# 13-Experimental.net
KiCad netlist of a schematic drawn in Altium Designer
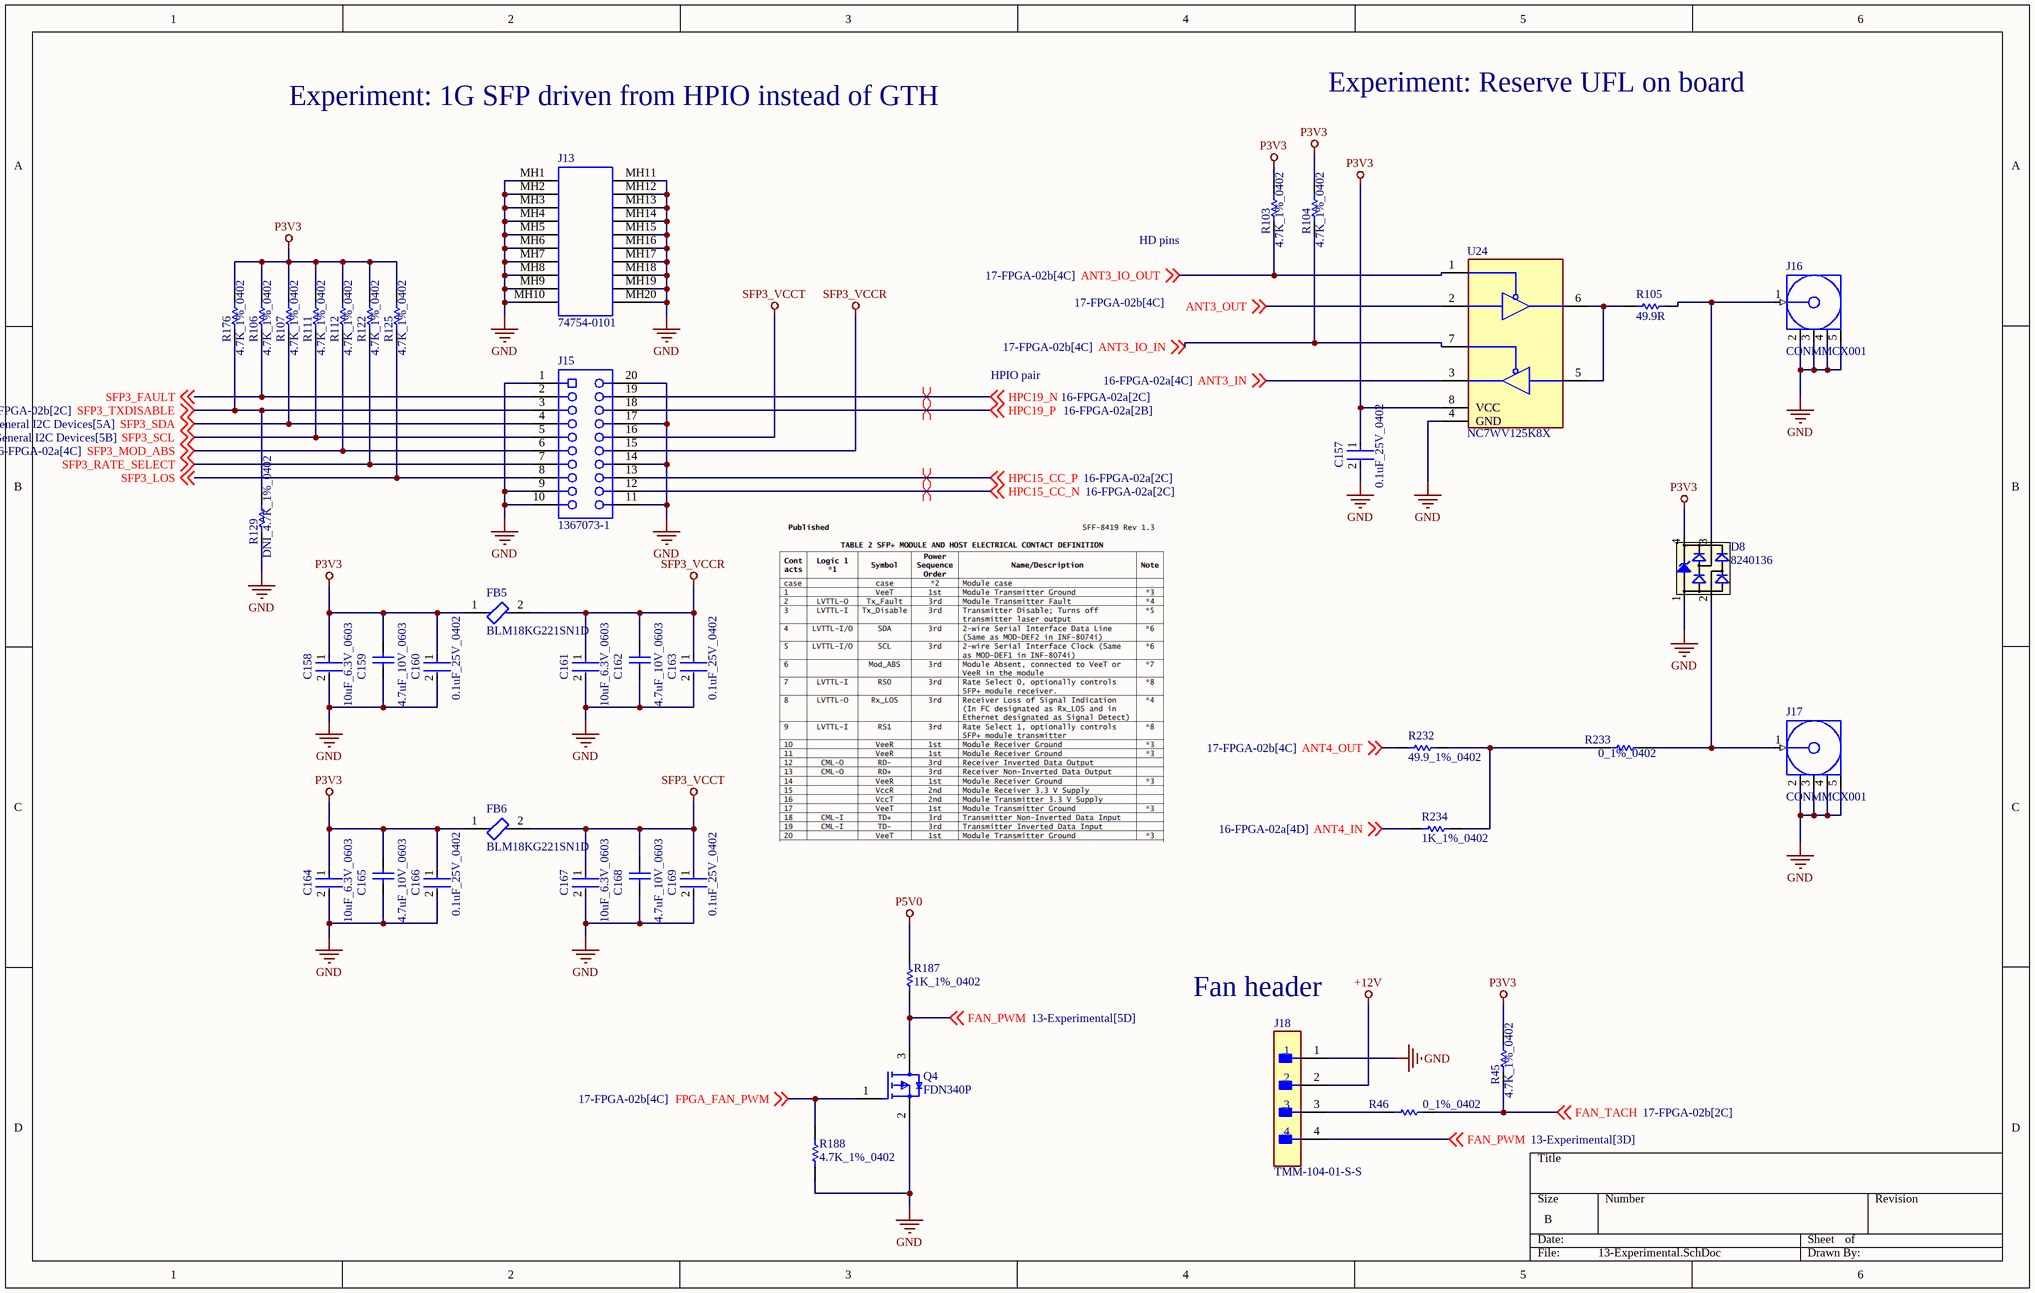
[diagram p0: 13-Experimental.SchDoc]

(export (version "E")
  (design (tool "Eeschema 10.0.6"))
  (components
    (comp (ref "C157")
      (value "0.1uF_25V_0402")
      (footprint "FP-0402-L_1_0_1-W_0_5_0_1-IPC_C")
      (description "General Purpose Ceramic Capacitor, 0402, 100nF, 10%, X7R, 15%, 25V")
      (fields (field (name "VOLTAGE") "25V") (field (name "TOLERANCE") "10%"))
      (libsource (lib "Altium Content Vault") (part "b4654b650e69147ec39a6b967a45e02"))
    )
    (comp (ref "C158")
      (value "10uF_6.3V_0603")
      (footprint "FP-C0603C106M9PACTU-MFG")
      (description "CAP CER 10UF 6.3V X5R 0603")
      (fields
        (field (name "MANUFACTURER PART NUMBER") "C0603C106M9PACTU")
        (field (name "MANUFACTURER") "Kemet")
      )
      (libsource (lib "Altium Content Vault") (part "b4654b650e69147ec39a6b967a45e02"))
    )
    (comp (ref "C159")
      (value "4.7uF_10V_0603")
      (footprint "CAPC1608X87X35NL15T15")
      (fields (field (name "PART NUMBER") "C0603C475K8PACTU") (field (name "MANUFACTURER") "Kemet"))
      (libsource (lib "Altium Content Vault") (part "CAP"))
    )
    (comp (ref "C160")
      (value "0.1uF_25V_0402")
      (footprint "FP-0402-L_1_0_1-W_0_5_0_1-IPC_C")
      (description "General Purpose Ceramic Capacitor, 0402, 100nF, 10%, X7R, 15%, 25V")
      (fields (field (name "VOLTAGE") "25V") (field (name "TOLERANCE") "10%"))
      (libsource (lib "Altium Content Vault") (part "b4654b650e69147ec39a6b967a45e02"))
    )
    (comp (ref "C161")
      (value "10uF_6.3V_0603")
      (footprint "FP-C0603C106M9PACTU-MFG")
      (description "CAP CER 10UF 6.3V X5R 0603")
      (fields
        (field (name "MANUFACTURER PART NUMBER") "C0603C106M9PACTU")
        (field (name "MANUFACTURER") "Kemet")
      )
      (libsource (lib "Altium Content Vault") (part "b4654b650e69147ec39a6b967a45e02"))
    )
    (comp (ref "C162")
      (value "4.7uF_10V_0603")
      (footprint "CAPC1608X87X35NL15T15")
      (fields (field (name "PART NUMBER") "C0603C475K8PACTU") (field (name "MANUFACTURER") "Kemet"))
      (libsource (lib "Altium Content Vault") (part "CAP"))
    )
    (comp (ref "C163")
      (value "0.1uF_25V_0402")
      (footprint "FP-0402-L_1_0_1-W_0_5_0_1-IPC_C")
      (description "General Purpose Ceramic Capacitor, 0402, 100nF, 10%, X7R, 15%, 25V")
      (fields (field (name "VOLTAGE") "25V") (field (name "TOLERANCE") "10%"))
      (libsource (lib "Altium Content Vault") (part "b4654b650e69147ec39a6b967a45e02"))
    )
    (comp (ref "C164")
      (value "10uF_6.3V_0603")
      (footprint "FP-C0603C106M9PACTU-MFG")
      (description "CAP CER 10UF 6.3V X5R 0603")
      (fields
        (field (name "MANUFACTURER PART NUMBER") "C0603C106M9PACTU")
        (field (name "MANUFACTURER") "Kemet")
      )
      (libsource (lib "Altium Content Vault") (part "b4654b650e69147ec39a6b967a45e02"))
    )
    (comp (ref "C165")
      (value "4.7uF_10V_0603")
      (footprint "CAPC1608X87X35NL15T15")
      (fields (field (name "PART NUMBER") "C0603C475K8PACTU") (field (name "MANUFACTURER") "Kemet"))
      (libsource (lib "Altium Content Vault") (part "CAP"))
    )
    (comp (ref "C166")
      (value "0.1uF_25V_0402")
      (footprint "FP-0402-L_1_0_1-W_0_5_0_1-IPC_C")
      (description "General Purpose Ceramic Capacitor, 0402, 100nF, 10%, X7R, 15%, 25V")
      (fields (field (name "VOLTAGE") "25V") (field (name "TOLERANCE") "10%"))
      (libsource (lib "Altium Content Vault") (part "b4654b650e69147ec39a6b967a45e02"))
    )
    (comp (ref "C167")
      (value "10uF_6.3V_0603")
      (footprint "FP-C0603C106M9PACTU-MFG")
      (description "CAP CER 10UF 6.3V X5R 0603")
      (fields
        (field (name "MANUFACTURER PART NUMBER") "C0603C106M9PACTU")
        (field (name "MANUFACTURER") "Kemet")
      )
      (libsource (lib "Altium Content Vault") (part "b4654b650e69147ec39a6b967a45e02"))
    )
    (comp (ref "C168")
      (value "4.7uF_10V_0603")
      (footprint "CAPC1608X87X35NL15T15")
      (fields (field (name "PART NUMBER") "C0603C475K8PACTU") (field (name "MANUFACTURER") "Kemet"))
      (libsource (lib "Altium Content Vault") (part "CAP"))
    )
    (comp (ref "C169")
      (value "0.1uF_25V_0402")
      (footprint "FP-0402-L_1_0_1-W_0_5_0_1-IPC_C")
      (description "General Purpose Ceramic Capacitor, 0402, 100nF, 10%, X7R, 15%, 25V")
      (fields (field (name "VOLTAGE") "25V") (field (name "TOLERANCE") "10%"))
      (libsource (lib "Altium Content Vault") (part "b4654b650e69147ec39a6b967a45e02"))
    )
    (comp (ref "D8")
      (value "8240136")
      (footprint "SOT143-4L")
      (description "TVS Diode WE-TVS-HS, VRWM=3.3V")
      (fields (field (name "MANUFACTURER") "Wuerth Elektronik"))
      (libsource (lib "Altium Content Vault") (part "WE-TVS-HS-4"))
    )
    (comp (ref "FB5")
      (value "BLM18KG221SN1D")
      (footprint "FP-BLM18-0_15-t0_8-IPC_B")
      (description "Chip Ferrite Bead, 0603, 220Ω @ 100MHz, 0.05Ω, 25%, 2.2A")
      (fields (field (name "TOLERANCE") "25%"))
      (libsource (lib "Altium Content Vault") (part "5f30dd21d616792df468990f7003faa"))
    )
    (comp (ref "FB6")
      (value "BLM18KG221SN1D")
      (footprint "FP-BLM18-0_15-t0_8-IPC_B")
      (description "Chip Ferrite Bead, 0603, 220Ω @ 100MHz, 0.05Ω, 25%, 2.2A")
      (fields (field (name "TOLERANCE") "25%"))
      (libsource (lib "Altium Content Vault") (part "5f30dd21d616792df468990f7003faa"))
    )
    (comp (ref "J13")
      (value "74754-0101")
      (footprint "MOLX-74754-0101_V")
      (description "SFP+ Cage, Single Port, Height 10.85 mm, Tail Height 3.05 mm, -40 to 85 degC, RoHS, Tray")
      (libsource (lib "Altium Content Vault") (part "MOLX-74754-0101"))
    )
    (comp (ref "J15")
      (value "1367073-1")
      (footprint "TECO-1367073-1_V")
      (fields (field (name "MANUFACTURER") "TE Connectivity"))
      (libsource (lib "Altium Content Vault") (part "CN-2P-F-R20_B"))
    )
    (comp (ref "J16")
      (value "CONMMCX001")
      (footprint "CON-MMCX")
      (description "MMCX Female PCB Mount Connector, Thru-Hole")
      (libsource (lib "Altium Content Vault") (part "CN-1P-F-RF5"))
    )
    (comp (ref "J17")
      (value "CONMMCX001")
      (footprint "CON-MMCX")
      (description "MMCX Female PCB Mount Connector, Thru-Hole")
      (libsource (lib "Altium Content Vault") (part "CN-1P-F-RF5"))
    )
    (comp (ref "J18")
      (value "TMM-104-01-S-S")
      (footprint "FP-TMM-104-01-S-S-MFG")
      (description "CONN HEADER VERT 4POS 2MM")
      (libsource (lib "Altium Content Vault") (part "299a8cea1bdcbc3624fe62c390fa72c"))
    )
    (comp (ref "Q4")
      (value "FDN340P")
      (footprint "FP-527AG-MFG")
      (description "MOSFET P-CH 20V 2A SSOT3")
      (libsource (lib "Altium Content Vault") (part "d23f43cc42f60b967b7caccf14518fd"))
    )
    (comp (ref "R45")
      (value "4.7K_1%_0402")
      (footprint "RESC1005X40X25NL10T10")
      (fields (field (name "MANUFACTURER") "Bourns") (field (name "PART NUMBER") "CR0402-FX-4701GLF"))
      (libsource (lib "Altium Content Vault") (part "RES"))
    )
    (comp (ref "R46")
      (value "0_1%_0402")
      (footprint "RESC1005X40X25LL05T05")
      (description "Chip Resistor, 0 Ohm, 0.1 W, -55 to 155 degC, 0402 (1005 Metric), RoHS, Tape and Reel")
      (fields (field (name "MANUFACTURER") "Panasonic") (field (name "TOLERANCE") "5%"))
      (libsource (lib "Altium Content Vault") (part "RES-2"))
    )
    (comp (ref "R103")
      (value "4.7K_1%_0402")
      (footprint "RESC1005X40X25NL10T10")
      (fields (field (name "MANUFACTURER") "Bourns") (field (name "PART NUMBER") "CR0402-FX-4701GLF"))
      (libsource (lib "Altium Content Vault") (part "RES"))
    )
    (comp (ref "R104")
      (value "4.7K_1%_0402")
      (footprint "RESC1005X40X25NL10T10")
      (fields (field (name "MANUFACTURER") "Bourns") (field (name "PART NUMBER") "CR0402-FX-4701GLF"))
      (libsource (lib "Altium Content Vault") (part "RES"))
    )
    (comp (ref "R105")
      (value "49.9R")
      (footprint "RESC1608X55X25NL10T15")
      (libsource (lib "Altium Content Vault") (part "RES-2"))
    )
    (comp (ref "R106")
      (value "4.7K_1%_0402")
      (footprint "RESC1005X40X25NL10T10")
      (fields (field (name "MANUFACTURER") "Bourns") (field (name "PART NUMBER") "CR0402-FX-4701GLF"))
      (libsource (lib "Altium Content Vault") (part "RES"))
    )
    (comp (ref "R107")
      (value "4.7K_1%_0402")
      (footprint "RESC1005X40X25NL10T10")
      (fields (field (name "MANUFACTURER") "Bourns") (field (name "PART NUMBER") "CR0402-FX-4701GLF"))
      (libsource (lib "Altium Content Vault") (part "RES"))
    )
    (comp (ref "R111")
      (value "4.7K_1%_0402")
      (footprint "RESC1005X40X25NL10T10")
      (fields (field (name "MANUFACTURER") "Bourns") (field (name "PART NUMBER") "CR0402-FX-4701GLF"))
      (libsource (lib "Altium Content Vault") (part "RES"))
    )
    (comp (ref "R112")
      (value "4.7K_1%_0402")
      (footprint "RESC1005X40X25NL10T10")
      (fields (field (name "MANUFACTURER") "Bourns") (field (name "PART NUMBER") "CR0402-FX-4701GLF"))
      (libsource (lib "Altium Content Vault") (part "RES"))
    )
    (comp (ref "R122")
      (value "4.7K_1%_0402")
      (footprint "RESC1005X40X25NL10T10")
      (fields (field (name "MANUFACTURER") "Bourns") (field (name "PART NUMBER") "CR0402-FX-4701GLF"))
      (libsource (lib "Altium Content Vault") (part "RES"))
    )
    (comp (ref "R125")
      (value "4.7K_1%_0402")
      (footprint "RESC1005X40X25NL10T10")
      (fields (field (name "MANUFACTURER") "Bourns") (field (name "PART NUMBER") "CR0402-FX-4701GLF"))
      (libsource (lib "Altium Content Vault") (part "RES"))
    )
    (comp (ref "R129")
      (value "DNI_4.7K_1%_0402")
      (footprint "RESC1005X40X25NL10T10")
      (fields (field (name "MANUFACTURER") "Bourns") (field (name "PART NUMBER") "CR0402-FX-4701GLF"))
      (libsource (lib "Altium Content Vault") (part "RES"))
    )
    (comp (ref "R176")
      (value "4.7K_1%_0402")
      (footprint "RESC1005X40X25NL10T10")
      (fields (field (name "MANUFACTURER") "Bourns") (field (name "PART NUMBER") "CR0402-FX-4701GLF"))
      (libsource (lib "Altium Content Vault") (part "RES"))
    )
    (comp (ref "R187")
      (value "1K_1%_0402")
      (footprint "RESC1005X40X25NL05T05")
      (fields (field (name "MANUFACTURER") "Vishay Dale") (field (name "PART NUMBER") "CRCW04021K00FKTD"))
      (libsource (lib "Altium Content Vault") (part "RES"))
    )
    (comp (ref "R188")
      (value "4.7K_1%_0402")
      (footprint "RESC1005X40X25NL10T10")
      (fields (field (name "MANUFACTURER") "Bourns") (field (name "PART NUMBER") "CR0402-FX-4701GLF"))
      (libsource (lib "Altium Content Vault") (part "RES"))
    )
    (comp (ref "R232")
      (value "49.9_1%_0402")
      (footprint "RESC1005X40X25NL10T10")
      (fields (field (name "PART NUMBER") "RK73H1ETTP49R9F") (field (name "MANUFACTURER") "KOA Speer"))
      (libsource (lib "Altium Content Vault") (part "RES"))
    )
    (comp (ref "R233")
      (value "0_1%_0402")
      (footprint "RESC1005X40X25LL05T05")
      (description "Chip Resistor, 0 Ohm, 0.1 W, -55 to 155 degC, 0402 (1005 Metric), RoHS, Tape and Reel")
      (fields (field (name "MANUFACTURER") "Panasonic") (field (name "TOLERANCE") "5%"))
      (libsource (lib "Altium Content Vault") (part "RES-2"))
    )
    (comp (ref "R234")
      (value "1K_1%_0402")
      (footprint "RESC1005X40X25NL05T05")
      (fields (field (name "MANUFACTURER") "Vishay Dale") (field (name "PART NUMBER") "CRCW04021K00FKTD"))
      (libsource (lib "Altium Content Vault") (part "RES"))
    )
    (comp (ref "U24")
      (value "NC7WV125K8X")
      (footprint "SOP50P310X90-8N")
      (description "Integrated Circuit")
      (fields (field (name "MOUSER PART NUMBER") "512-NC7WV125K8X"))
      (libsource (lib "SamacSys") (part "NC7WV125K8X"))
    )
  )
  (nets
    (net (code "1") (name "+12V") (class "Default")
      (node (ref "J18") (pin "2") (pinfunction "2_2") (pintype "passive"))
    )
    (net (code "2") (name "ANT3_IN") (class "Default") (node (ref "U24") (pin "3") (pintype "passive")))
    (net (code "3") (name "ANT3_IO_IN") (class "Default")
      (node (ref "R104") (pin "2") (pinfunction "2_2") (pintype "passive"))
      (node (ref "U24") (pin "7") (pintype "passive"))
    )
    (net (code "4") (name "ANT3_IO_OUT") (class "Default")
      (node (ref "R103") (pin "2") (pinfunction "2_2") (pintype "passive"))
      (node (ref "U24") (pin "1") (pintype "passive"))
    )
    (net (code "5") (name "ANT3_OUT") (class "Default") (node (ref "U24") (pin "2") (pintype "passive")))
    (net (code "6") (name "ANT4_IN") (class "Default")
      (node (ref "R234") (pin "1") (pinfunction "1_1") (pintype "passive"))
    )
    (net (code "7") (name "ANT4_OUT") (class "Default")
      (node (ref "R232") (pin "1") (pinfunction "1_1") (pintype "passive"))
    )
    (net (code "8") (name "FAN_PWM") (class "Default")
      (node (ref "J18") (pin "4") (pinfunction "4_4") (pintype "passive"))
      (node (ref "Q4") (pin "3") (pinfunction "D_3") (pintype "passive"))
      (node (ref "R187") (pin "1") (pinfunction "1_1") (pintype "passive"))
    )
    (net (code "9") (name "FAN_TACH") (class "Default")
      (node (ref "R45") (pin "2") (pinfunction "2_2") (pintype "passive"))
      (node (ref "R46") (pin "2") (pinfunction "2_2") (pintype "passive"))
    )
    (net (code "10") (name "FPGA_FAN_PWM") (class "Default")
      (node (ref "Q4") (pin "1") (pinfunction "G_1") (pintype "passive"))
      (node (ref "R188") (pin "2") (pinfunction "2_2") (pintype "passive"))
    )
    (net (code "11") (name "GND") (class "Default")
      (node (ref "C157") (pin "2") (pinfunction "2_2") (pintype "passive"))
      (node (ref "C158") (pin "2") (pinfunction "2_2") (pintype "passive"))
      (node (ref "C159") (pin "1") (pinfunction "1_1") (pintype "passive"))
      (node (ref "C160") (pin "2") (pinfunction "2_2") (pintype "passive"))
      (node (ref "C161") (pin "2") (pinfunction "2_2") (pintype "passive"))
      (node (ref "C162") (pin "1") (pinfunction "1_1") (pintype "passive"))
      (node (ref "C163") (pin "2") (pinfunction "2_2") (pintype "passive"))
      (node (ref "C164") (pin "2") (pinfunction "2_2") (pintype "passive"))
      (node (ref "C165") (pin "1") (pinfunction "1_1") (pintype "passive"))
      (node (ref "C166") (pin "2") (pinfunction "2_2") (pintype "passive"))
      (node (ref "C167") (pin "2") (pinfunction "2_2") (pintype "passive"))
      (node (ref "C168") (pin "1") (pinfunction "1_1") (pintype "passive"))
      (node (ref "C169") (pin "2") (pinfunction "2_2") (pintype "passive"))
      (node (ref "D8") (pin "1") (pinfunction "GND_1") (pintype "passive"))
      (node (ref "J13") (pin "MH1") (pinfunction "MH1_MH1") (pintype "passive"))
      (node (ref "J13") (pin "MH10") (pinfunction "MH10_MH10") (pintype "passive"))
      (node (ref "J13") (pin "MH11") (pinfunction "MH11_MH11") (pintype "passive"))
      (node (ref "J13") (pin "MH12") (pinfunction "MH12_MH12") (pintype "passive"))
      (node (ref "J13") (pin "MH13") (pinfunction "MH13_MH13") (pintype "passive"))
      (node (ref "J13") (pin "MH14") (pinfunction "MH14_MH14") (pintype "passive"))
      (node (ref "J13") (pin "MH15") (pinfunction "MH15_MH15") (pintype "passive"))
      (node (ref "J13") (pin "MH16") (pinfunction "MH16_MH16") (pintype "passive"))
      (node (ref "J13") (pin "MH17") (pinfunction "MH17_MH17") (pintype "passive"))
      (node (ref "J13") (pin "MH18") (pinfunction "MH18_MH18") (pintype "passive"))
      (node (ref "J13") (pin "MH19") (pinfunction "MH19_MH19") (pintype "passive"))
      (node (ref "J13") (pin "MH2") (pinfunction "MH2_MH2") (pintype "passive"))
      (node (ref "J13") (pin "MH20") (pinfunction "MH20_MH20") (pintype "passive"))
      (node (ref "J13") (pin "MH3") (pinfunction "MH3_MH3") (pintype "passive"))
      (node (ref "J13") (pin "MH4") (pinfunction "MH4_MH4") (pintype "passive"))
      (node (ref "J13") (pin "MH5") (pinfunction "MH5_MH5") (pintype "passive"))
      (node (ref "J13") (pin "MH6") (pinfunction "MH6_MH6") (pintype "passive"))
      (node (ref "J13") (pin "MH7") (pinfunction "MH7_MH7") (pintype "passive"))
      (node (ref "J13") (pin "MH8") (pinfunction "MH8_MH8") (pintype "passive"))
      (node (ref "J13") (pin "MH9") (pinfunction "MH9_MH9") (pintype "passive"))
      (node (ref "J15") (pin "1") (pinfunction "1_1") (pintype "passive"))
      (node (ref "J15") (pin "10") (pinfunction "10_10") (pintype "passive"))
      (node (ref "J15") (pin "11") (pinfunction "11_11") (pintype "passive"))
      (node (ref "J15") (pin "14") (pinfunction "14_14") (pintype "passive"))
      (node (ref "J15") (pin "17") (pinfunction "17_17") (pintype "passive"))
      (node (ref "J15") (pin "20") (pinfunction "20_20") (pintype "passive"))
      (node (ref "J15") (pin "9") (pinfunction "9_9") (pintype "passive"))
      (node (ref "J16") (pin "2") (pinfunction "GND_2") (pintype "power_in"))
      (node (ref "J16") (pin "3") (pinfunction "GND_3") (pintype "power_in"))
      (node (ref "J16") (pin "4") (pinfunction "GND_4") (pintype "power_in"))
      (node (ref "J16") (pin "5") (pinfunction "GND_5") (pintype "power_in"))
      (node (ref "J17") (pin "2") (pinfunction "GND_2") (pintype "power_in"))
      (node (ref "J17") (pin "3") (pinfunction "GND_3") (pintype "power_in"))
      (node (ref "J17") (pin "4") (pinfunction "GND_4") (pintype "power_in"))
      (node (ref "J17") (pin "5") (pinfunction "GND_5") (pintype "power_in"))
      (node (ref "J18") (pin "1") (pinfunction "1_1") (pintype "passive"))
      (node (ref "Q4") (pin "2") (pinfunction "S_2") (pintype "passive"))
      (node (ref "R129") (pin "2") (pinfunction "2_2") (pintype "passive"))
      (node (ref "R188") (pin "1") (pinfunction "1_1") (pintype "passive"))
      (node (ref "U24") (pin "4") (pinfunction "GND_4") (pintype "passive"))
    )
    (net (code "12") (name "HPC15_CC_N") (class "Default")
      (node (ref "J15") (pin "12") (pinfunction "12_12") (pintype "passive"))
    )
    (net (code "13") (name "HPC15_CC_P") (class "Default")
      (node (ref "J15") (pin "13") (pinfunction "13_13") (pintype "passive"))
    )
    (net (code "14") (name "HPC19_N") (class "Default")
      (node (ref "J15") (pin "19") (pinfunction "19_19") (pintype "passive"))
    )
    (net (code "15") (name "HPC19_P") (class "Default")
      (node (ref "J15") (pin "18") (pinfunction "18_18") (pintype "passive"))
    )
    (net (code "16") (name "Net-(D8-I{slash}O1)") (class "Default")
      (node (ref "D8") (pin "2") (pinfunction "I/O1_2") (pintype "passive"))
      (node (ref "J17") (pin "1") (pinfunction "Signal_1") (pintype "input"))
      (node (ref "R233") (pin "2") (pinfunction "2_2") (pintype "passive"))
    )
    (net (code "17") (name "Net-(D8-I{slash}O2)") (class "Default")
      (node (ref "D8") (pin "3") (pinfunction "I/O2_3") (pintype "passive"))
      (node (ref "J16") (pin "1") (pinfunction "Signal_1") (pintype "input"))
      (node (ref "R105") (pin "2") (pinfunction "2_2") (pintype "passive"))
    )
    (net (code "18") (name "Net-(J18-Pad3)") (class "Default")
      (node (ref "J18") (pin "3") (pinfunction "3_3") (pintype "passive"))
      (node (ref "R46") (pin "1") (pinfunction "1_1") (pintype "passive"))
    )
    (net (code "19") (name "Net-(R105-Pad1)") (class "Default")
      (node (ref "R105") (pin "1") (pinfunction "1_1") (pintype "passive"))
      (node (ref "U24") (pin "5") (pintype "passive"))
      (node (ref "U24") (pin "6") (pintype "passive"))
    )
    (net (code "20") (name "Net-(R232-Pad2)") (class "Default")
      (node (ref "R232") (pin "2") (pinfunction "2_2") (pintype "passive"))
      (node (ref "R233") (pin "1") (pinfunction "1_1") (pintype "passive"))
      (node (ref "R234") (pin "2") (pinfunction "2_2") (pintype "passive"))
    )
    (net (code "21") (name "P3V3") (class "Default")
      (node (ref "C157") (pin "1") (pinfunction "1_1") (pintype "passive"))
      (node (ref "C158") (pin "1") (pinfunction "1_1") (pintype "passive"))
      (node (ref "C159") (pin "2") (pinfunction "2_2") (pintype "passive"))
      (node (ref "C160") (pin "1") (pinfunction "1_1") (pintype "passive"))
      (node (ref "C164") (pin "1") (pinfunction "1_1") (pintype "passive"))
      (node (ref "C165") (pin "2") (pinfunction "2_2") (pintype "passive"))
      (node (ref "C166") (pin "1") (pinfunction "1_1") (pintype "passive"))
      (node (ref "D8") (pin "4") (pinfunction "VDD_4") (pintype "passive"))
      (node (ref "FB5") (pin "1") (pinfunction "1_1") (pintype "passive"))
      (node (ref "FB6") (pin "1") (pinfunction "1_1") (pintype "passive"))
      (node (ref "R103") (pin "1") (pinfunction "1_1") (pintype "passive"))
      (node (ref "R104") (pin "1") (pinfunction "1_1") (pintype "passive"))
      (node (ref "R106") (pin "1") (pinfunction "1_1") (pintype "passive"))
      (node (ref "R107") (pin "1") (pinfunction "1_1") (pintype "passive"))
      (node (ref "R111") (pin "1") (pinfunction "1_1") (pintype "passive"))
      (node (ref "R112") (pin "1") (pinfunction "1_1") (pintype "passive"))
      (node (ref "R122") (pin "1") (pinfunction "1_1") (pintype "passive"))
      (node (ref "R125") (pin "1") (pinfunction "1_1") (pintype "passive"))
      (node (ref "R176") (pin "1") (pinfunction "1_1") (pintype "passive"))
      (node (ref "R45") (pin "1") (pinfunction "1_1") (pintype "passive"))
      (node (ref "U24") (pin "8") (pinfunction "VCC_8") (pintype "passive"))
    )
    (net (code "22") (name "P5V0") (class "Default")
      (node (ref "R187") (pin "2") (pinfunction "2_2") (pintype "passive"))
    )
    (net (code "23") (name "SFP3_FAULT") (class "Default")
      (node (ref "J15") (pin "2") (pinfunction "2_2") (pintype "passive"))
      (node (ref "R106") (pin "2") (pinfunction "2_2") (pintype "passive"))
    )
    (net (code "24") (name "SFP3_LOS") (class "Default")
      (node (ref "J15") (pin "8") (pinfunction "8_8") (pintype "passive"))
      (node (ref "R125") (pin "2") (pinfunction "2_2") (pintype "passive"))
    )
    (net (code "25") (name "SFP3_MOD_ABS") (class "Default")
      (node (ref "J15") (pin "6") (pinfunction "6_6") (pintype "passive"))
      (node (ref "R112") (pin "2") (pinfunction "2_2") (pintype "passive"))
    )
    (net (code "26") (name "SFP3_RATE_SELECT") (class "Default")
      (node (ref "J15") (pin "7") (pinfunction "7_7") (pintype "passive"))
      (node (ref "R122") (pin "2") (pinfunction "2_2") (pintype "passive"))
    )
    (net (code "27") (name "SFP3_SCL") (class "Default")
      (node (ref "J15") (pin "5") (pinfunction "5_5") (pintype "passive"))
      (node (ref "R111") (pin "2") (pinfunction "2_2") (pintype "passive"))
    )
    (net (code "28") (name "SFP3_SDA") (class "Default")
      (node (ref "J15") (pin "4") (pinfunction "4_4") (pintype "passive"))
      (node (ref "R107") (pin "2") (pinfunction "2_2") (pintype "passive"))
    )
    (net (code "29") (name "SFP3_TXDISABLE") (class "Default")
      (node (ref "J15") (pin "3") (pinfunction "3_3") (pintype "passive"))
      (node (ref "R129") (pin "1") (pinfunction "1_1") (pintype "passive"))
      (node (ref "R176") (pin "2") (pinfunction "2_2") (pintype "passive"))
    )
    (net (code "30") (name "SFP3_VCCR") (class "Default")
      (node (ref "C161") (pin "1") (pinfunction "1_1") (pintype "passive"))
      (node (ref "C162") (pin "2") (pinfunction "2_2") (pintype "passive"))
      (node (ref "C163") (pin "1") (pinfunction "1_1") (pintype "passive"))
      (node (ref "FB5") (pin "2") (pinfunction "2_2") (pintype "passive"))
      (node (ref "J15") (pin "15") (pinfunction "15_15") (pintype "passive"))
    )
    (net (code "31") (name "SFP3_VCCT") (class "Default")
      (node (ref "C167") (pin "1") (pinfunction "1_1") (pintype "passive"))
      (node (ref "C168") (pin "2") (pinfunction "2_2") (pintype "passive"))
      (node (ref "C169") (pin "1") (pinfunction "1_1") (pintype "passive"))
      (node (ref "FB6") (pin "2") (pinfunction "2_2") (pintype "passive"))
      (node (ref "J15") (pin "16") (pinfunction "16_16") (pintype "passive"))
    )
  )
)
